# PHY.net
KiCad netlist of a schematic drawn in Altium Designer
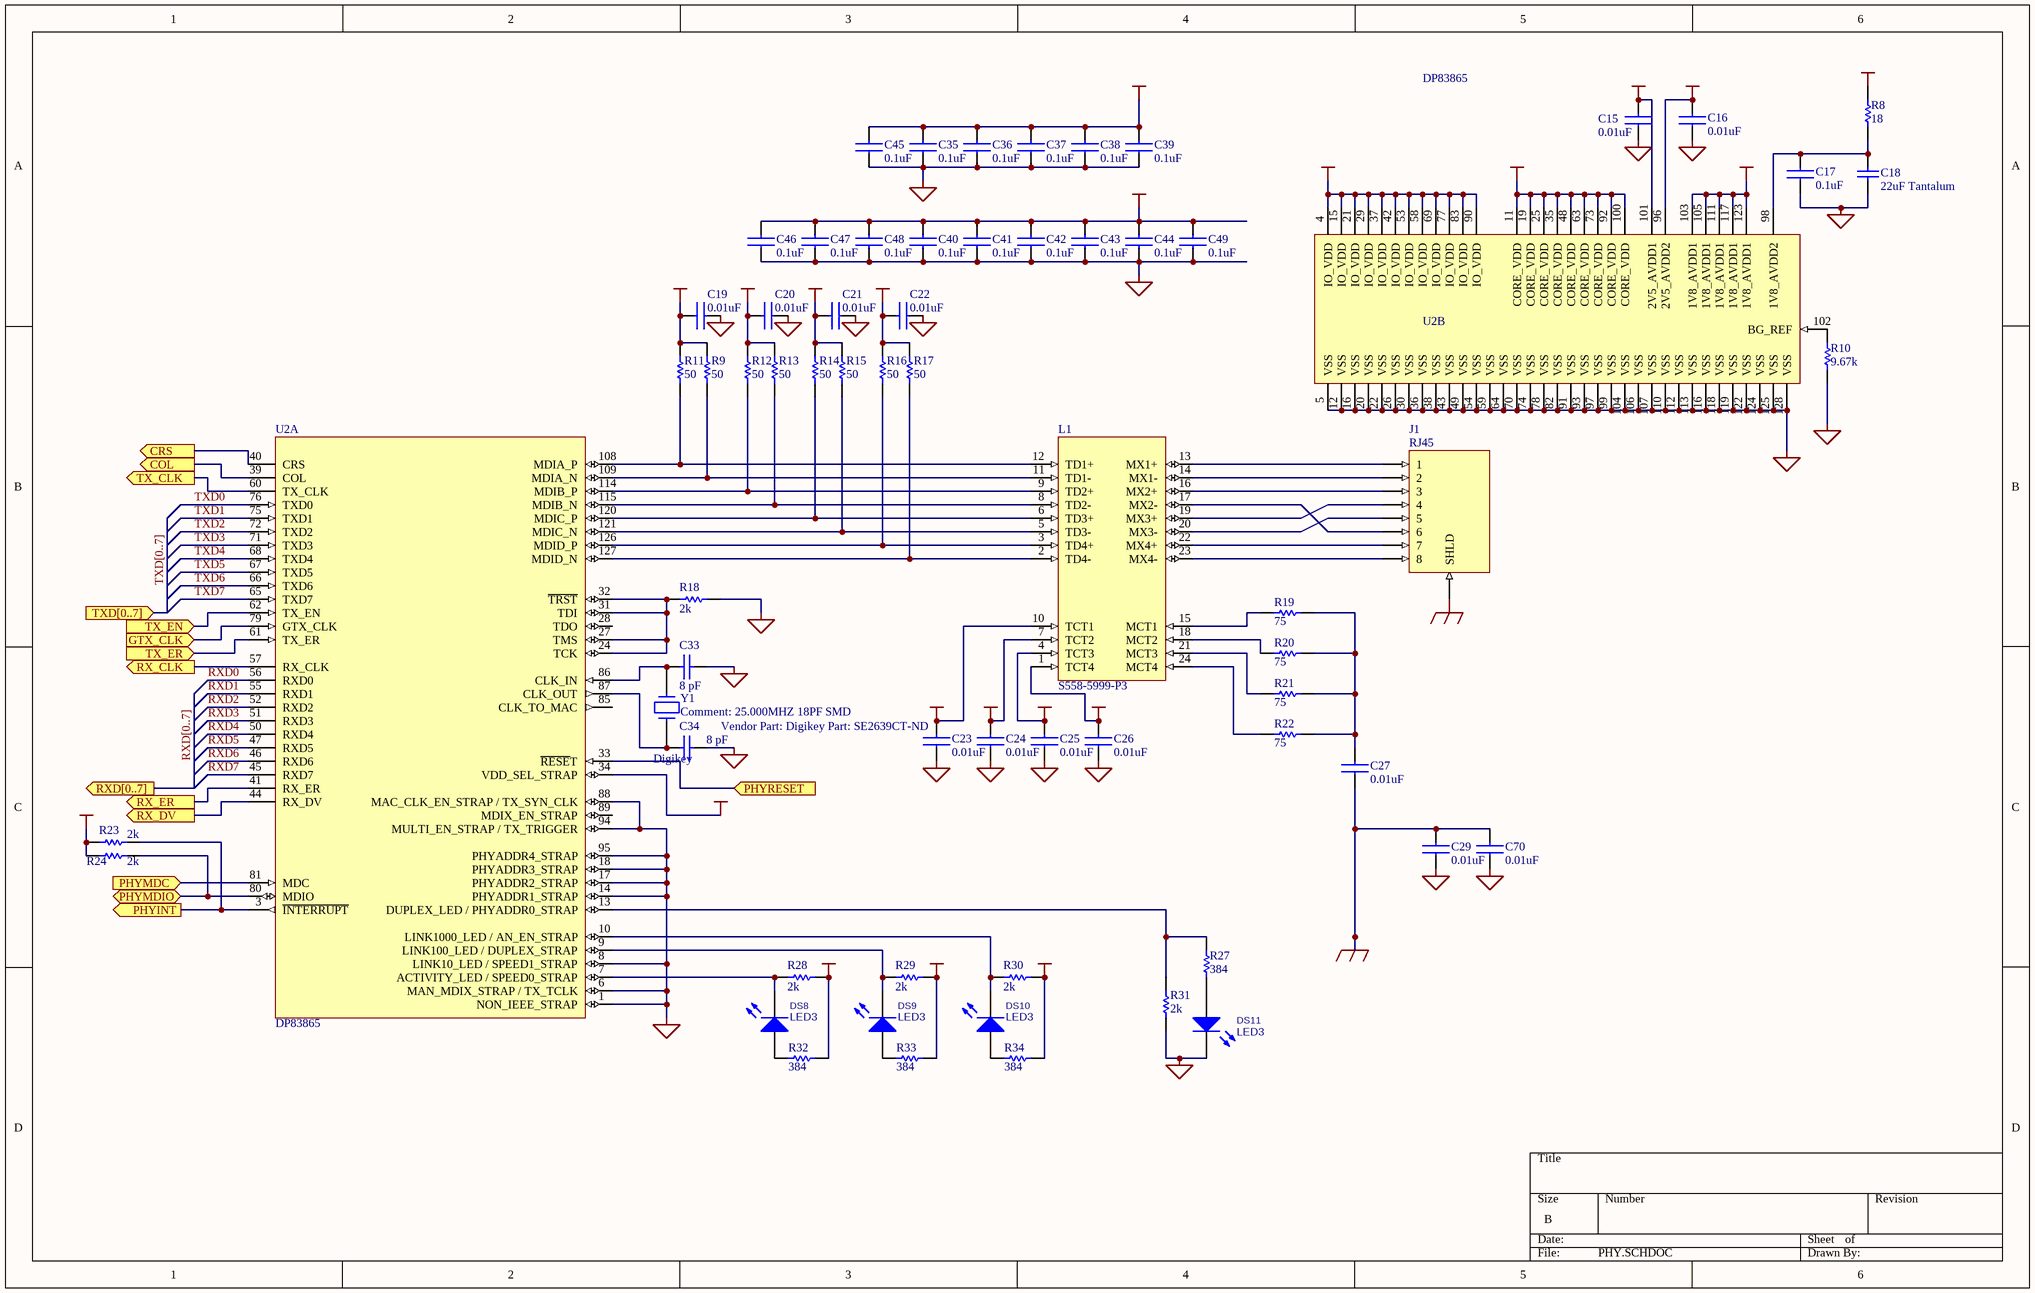
[diagram p0: PHY.SCHDOC]

(export (version "E")
  (design (tool "Eeschema 10.0.6"))
  (components
    (comp (ref "C15")
      (value "0.01uF")
      (footprint "0402")
      (description "Standard Capacitor")
      (fields (field (name "Comment") "CAPACITOR"))
      (libsource (lib "parts") (part "CAPACITOR"))
    )
    (comp (ref "C16")
      (value "0.01uF")
      (footprint "0402")
      (description "Standard Capacitor")
      (fields (field (name "Comment") "CAPACITOR"))
      (libsource (lib "parts") (part "CAPACITOR"))
    )
    (comp (ref "C17")
      (value "0.1uF")
      (footprint "0603")
      (description "Standard Capacitor")
      (fields (field (name "Comment") "CAPACITOR"))
      (libsource (lib "parts") (part "CAPACITOR"))
    )
    (comp (ref "C18")
      (value "22uF Tantalum")
      (footprint "TC7343-2917")
      (description "Capacitor")
      (fields
        (field (name "MANUFACTURER") "Generic Components")
        (field (name "Comment") "Cap")
        (field (name "PUBLISHER") "Altium Limited")
      )
      (libsource (lib "Miscellaneous Devices") (part "Cap"))
    )
    (comp (ref "C19")
      (value "0.01uF")
      (footprint "0402")
      (description "Standard Capacitor")
      (fields (field (name "Comment") "CAPACITOR"))
      (libsource (lib "parts") (part "CAPACITOR"))
    )
    (comp (ref "C20")
      (value "0.01uF")
      (footprint "0402")
      (description "Standard Capacitor")
      (fields (field (name "Comment") "CAPACITOR"))
      (libsource (lib "parts") (part "CAPACITOR"))
    )
    (comp (ref "C21")
      (value "0.01uF")
      (footprint "0402")
      (description "Standard Capacitor")
      (fields (field (name "Comment") "CAPACITOR"))
      (libsource (lib "parts") (part "CAPACITOR"))
    )
    (comp (ref "C22")
      (value "0.01uF")
      (footprint "0402")
      (description "Standard Capacitor")
      (fields (field (name "Comment") "CAPACITOR"))
      (libsource (lib "parts") (part "CAPACITOR"))
    )
    (comp (ref "C23")
      (value "0.01uF")
      (footprint "0402")
      (description "Standard Capacitor")
      (fields (field (name "Comment") "CAPACITOR"))
      (libsource (lib "parts") (part "CAPACITOR"))
    )
    (comp (ref "C24")
      (value "0.01uF")
      (footprint "0402")
      (description "Standard Capacitor")
      (fields (field (name "Comment") "CAPACITOR"))
      (libsource (lib "parts") (part "CAPACITOR"))
    )
    (comp (ref "C25")
      (value "0.01uF")
      (footprint "0402")
      (description "Standard Capacitor")
      (fields (field (name "Comment") "CAPACITOR"))
      (libsource (lib "parts") (part "CAPACITOR"))
    )
    (comp (ref "C26")
      (value "0.01uF")
      (footprint "0402")
      (description "Standard Capacitor")
      (fields (field (name "Comment") "CAPACITOR"))
      (libsource (lib "parts") (part "CAPACITOR"))
    )
    (comp (ref "C27")
      (value "0.01uF")
      (footprint "0402")
      (description "Standard Capacitor")
      (fields (field (name "Comment") "CAPACITOR"))
      (libsource (lib "parts") (part "CAPACITOR"))
    )
    (comp (ref "C29")
      (value "0.01uF")
      (footprint "0402")
      (description "Standard Capacitor")
      (fields (field (name "Comment") "CAPACITOR"))
      (libsource (lib "parts") (part "CAPACITOR"))
    )
    (comp (ref "C33")
      (value "8 pF")
      (footprint "0603")
      (description "Capacitor")
      (libsource (lib "*") (part "CAP"))
    )
    (comp (ref "C34")
      (value "8 pF")
      (footprint "0603")
      (description "Capacitor")
      (libsource (lib "*") (part "CAP"))
    )
    (comp (ref "C35")
      (value "0.1uF")
      (footprint "0603")
      (description "Standard Capacitor")
      (fields (field (name "Comment") "CAPACITOR"))
      (libsource (lib "parts") (part "CAPACITOR"))
    )
    (comp (ref "C36")
      (value "0.1uF")
      (footprint "0603")
      (description "Standard Capacitor")
      (fields (field (name "Comment") "CAPACITOR"))
      (libsource (lib "parts") (part "CAPACITOR"))
    )
    (comp (ref "C37")
      (value "0.1uF")
      (footprint "0603")
      (description "Standard Capacitor")
      (fields (field (name "Comment") "CAPACITOR"))
      (libsource (lib "parts") (part "CAPACITOR"))
    )
    (comp (ref "C38")
      (value "0.1uF")
      (footprint "0603")
      (description "Standard Capacitor")
      (fields (field (name "Comment") "CAPACITOR"))
      (libsource (lib "parts") (part "CAPACITOR"))
    )
    (comp (ref "C39")
      (value "0.1uF")
      (footprint "0603")
      (description "Standard Capacitor")
      (fields (field (name "Comment") "CAPACITOR"))
      (libsource (lib "parts") (part "CAPACITOR"))
    )
    (comp (ref "C40")
      (value "0.1uF")
      (footprint "0603")
      (description "Standard Capacitor")
      (fields (field (name "Comment") "CAPACITOR"))
      (libsource (lib "parts") (part "CAPACITOR"))
    )
    (comp (ref "C41")
      (value "0.1uF")
      (footprint "0603")
      (description "Standard Capacitor")
      (fields (field (name "Comment") "CAPACITOR"))
      (libsource (lib "parts") (part "CAPACITOR"))
    )
    (comp (ref "C42")
      (value "0.1uF")
      (footprint "0603")
      (description "Standard Capacitor")
      (fields (field (name "Comment") "CAPACITOR"))
      (libsource (lib "parts") (part "CAPACITOR"))
    )
    (comp (ref "C43")
      (value "0.1uF")
      (footprint "0603")
      (description "Standard Capacitor")
      (fields (field (name "Comment") "CAPACITOR"))
      (libsource (lib "parts") (part "CAPACITOR"))
    )
    (comp (ref "C44")
      (value "0.1uF")
      (footprint "0603")
      (description "Standard Capacitor")
      (fields (field (name "Comment") "CAPACITOR"))
      (libsource (lib "parts") (part "CAPACITOR"))
    )
    (comp (ref "C45")
      (value "0.1uF")
      (footprint "0603")
      (description "Standard Capacitor")
      (fields (field (name "Comment") "CAPACITOR"))
      (libsource (lib "parts") (part "CAPACITOR"))
    )
    (comp (ref "C46")
      (value "0.1uF")
      (footprint "0603")
      (description "Standard Capacitor")
      (fields (field (name "Comment") "CAPACITOR"))
      (libsource (lib "parts") (part "CAPACITOR"))
    )
    (comp (ref "C47")
      (value "0.1uF")
      (footprint "0603")
      (description "Standard Capacitor")
      (fields (field (name "Comment") "CAPACITOR"))
      (libsource (lib "parts") (part "CAPACITOR"))
    )
    (comp (ref "C48")
      (value "0.1uF")
      (footprint "0603")
      (description "Standard Capacitor")
      (fields (field (name "Comment") "CAPACITOR"))
      (libsource (lib "parts") (part "CAPACITOR"))
    )
    (comp (ref "C49")
      (value "0.1uF")
      (footprint "0603")
      (description "Standard Capacitor")
      (fields (field (name "Comment") "CAPACITOR"))
      (libsource (lib "parts") (part "CAPACITOR"))
    )
    (comp (ref "C70")
      (value "0.01uF")
      (footprint "0402")
      (description "Standard Capacitor")
      (fields (field (name "Comment") "CAPACITOR"))
      (libsource (lib "parts") (part "CAPACITOR"))
    )
    (comp (ref "DS8")
      (value "LED3")
      (footprint "SMD _LED")
      (description "Typical BLUE SiC LED")
      (fields (field (name "PUBLISHER") "Altium Limited"))
      (libsource (lib "Miscellaneous Devices") (part "LED3"))
    )
    (comp (ref "DS9")
      (value "LED3")
      (footprint "SMD _LED")
      (description "Typical BLUE SiC LED")
      (fields (field (name "PUBLISHER") "Altium Limited"))
      (libsource (lib "Miscellaneous Devices") (part "LED3"))
    )
    (comp (ref "DS10")
      (value "LED3")
      (footprint "SMD _LED")
      (description "Typical BLUE SiC LED")
      (fields (field (name "PUBLISHER") "Altium Limited"))
      (libsource (lib "Miscellaneous Devices") (part "LED3"))
    )
    (comp (ref "DS11")
      (value "LED3")
      (footprint "SMD _LED")
      (description "Typical BLUE SiC LED")
      (fields (field (name "PUBLISHER") "Altium Limited"))
      (libsource (lib "Miscellaneous Devices") (part "LED3"))
    )
    (comp (ref "J1")
      (value "RJ45")
      (footprint "MOLEXRJ45_44050-0007")
      (description "RJ-45 connector")
      (libsource (lib "*") (part "RJ45"))
    )
    (comp (ref "L1")
      (value "S558-5999-P3")
      (footprint "S558-5999-P3")
      (description "BEL 1000base-T magnetics S588-5999-P3")
      (libsource (lib "My devices") (part "S558-5999-P3"))
    )
    (comp (ref "R8")
      (value "18")
      (footprint "0603")
      (description "Resistor")
      (fields
        (field (name "MANUFACTURER") "Generic Components")
        (field (name "Comment") "Res1")
        (field (name "PUBLISHER") "Altium Limited")
      )
      (libsource (lib "Miscellaneous Devices") (part "Res1"))
    )
    (comp (ref "R9")
      (value "50")
      (footprint "0603")
      (description "Standard Passive Resistor")
      (fields (field (name "TOLERANCE") "1%") (field (name "Comment") "RESISTOR"))
      (libsource (lib "parts") (part "RESISTOR"))
    )
    (comp (ref "R10")
      (value "9.67k")
      (footprint "0603")
      (description "Resistor")
      (fields
        (field (name "MANUFACTURER") "Generic Components")
        (field (name "Comment") "Res1")
        (field (name "PUBLISHER") "Altium Limited")
      )
      (libsource (lib "Miscellaneous Devices") (part "Res1"))
    )
    (comp (ref "R11")
      (value "50")
      (footprint "0603")
      (description "Standard Passive Resistor")
      (fields (field (name "TOLERANCE") "1%") (field (name "Comment") "RESISTOR"))
      (libsource (lib "parts") (part "RESISTOR"))
    )
    (comp (ref "R12")
      (value "50")
      (footprint "0603")
      (description "Standard Passive Resistor")
      (fields (field (name "TOLERANCE") "1%") (field (name "Comment") "RESISTOR"))
      (libsource (lib "parts") (part "RESISTOR"))
    )
    (comp (ref "R13")
      (value "50")
      (footprint "0603")
      (description "Standard Passive Resistor")
      (fields (field (name "TOLERANCE") "1%") (field (name "Comment") "RESISTOR"))
      (libsource (lib "parts") (part "RESISTOR"))
    )
    (comp (ref "R14")
      (value "50")
      (footprint "0603")
      (description "Standard Passive Resistor")
      (fields (field (name "TOLERANCE") "1%") (field (name "Comment") "RESISTOR"))
      (libsource (lib "parts") (part "RESISTOR"))
    )
    (comp (ref "R15")
      (value "50")
      (footprint "0603")
      (description "Standard Passive Resistor")
      (fields (field (name "TOLERANCE") "1%") (field (name "Comment") "RESISTOR"))
      (libsource (lib "parts") (part "RESISTOR"))
    )
    (comp (ref "R16")
      (value "50")
      (footprint "0603")
      (description "Standard Passive Resistor")
      (fields (field (name "TOLERANCE") "1%") (field (name "Comment") "RESISTOR"))
      (libsource (lib "parts") (part "RESISTOR"))
    )
    (comp (ref "R17")
      (value "50")
      (footprint "0603")
      (description "Standard Passive Resistor")
      (fields (field (name "TOLERANCE") "1%") (field (name "Comment") "RESISTOR"))
      (libsource (lib "parts") (part "RESISTOR"))
    )
    (comp (ref "R18")
      (value "2k")
      (footprint "0603")
      (description "Standard Passive Resistor")
      (fields (field (name "TOLERANCE") "1%") (field (name "Comment") "RESISTOR"))
      (libsource (lib "parts") (part "RESISTOR"))
    )
    (comp (ref "R19")
      (value "75")
      (footprint "0603")
      (description "Resistor")
      (fields
        (field (name "MANUFACTURER") "Generic Components")
        (field (name "Comment") "Res1")
        (field (name "PUBLISHER") "Altium Limited")
      )
      (libsource (lib "Miscellaneous Devices") (part "Res1"))
    )
    (comp (ref "R20")
      (value "75")
      (footprint "0603")
      (description "Resistor")
      (fields
        (field (name "MANUFACTURER") "Generic Components")
        (field (name "Comment") "Res1")
        (field (name "PUBLISHER") "Altium Limited")
      )
      (libsource (lib "Miscellaneous Devices") (part "Res1"))
    )
    (comp (ref "R21")
      (value "75")
      (footprint "0603")
      (description "Resistor")
      (fields
        (field (name "MANUFACTURER") "Generic Components")
        (field (name "Comment") "Res1")
        (field (name "PUBLISHER") "Altium Limited")
      )
      (libsource (lib "Miscellaneous Devices") (part "Res1"))
    )
    (comp (ref "R22")
      (value "75")
      (footprint "0603")
      (description "Resistor")
      (fields
        (field (name "MANUFACTURER") "Generic Components")
        (field (name "Comment") "Res1")
        (field (name "PUBLISHER") "Altium Limited")
      )
      (libsource (lib "Miscellaneous Devices") (part "Res1"))
    )
    (comp (ref "R23")
      (value "2k")
      (footprint "0603")
      (description "Standard Passive Resistor")
      (fields (field (name "TOLERANCE") "1%") (field (name "Comment") "RESISTOR"))
      (libsource (lib "parts") (part "RESISTOR"))
    )
    (comp (ref "R24")
      (value "2k")
      (footprint "0603")
      (description "Standard Passive Resistor")
      (fields (field (name "TOLERANCE") "1%") (field (name "Comment") "RESISTOR"))
      (libsource (lib "parts") (part "RESISTOR"))
    )
    (comp (ref "R27")
      (value "384")
      (footprint "0603")
      (description "Resistor")
      (fields
        (field (name "MANUFACTURER") "Generic Components")
        (field (name "Comment") "Res1")
        (field (name "PUBLISHER") "Altium Limited")
      )
      (libsource (lib "Miscellaneous Devices") (part "Res1"))
    )
    (comp (ref "R28")
      (value "2k")
      (footprint "0603")
      (description "Standard Passive Resistor")
      (fields (field (name "TOLERANCE") "1%") (field (name "Comment") "RESISTOR"))
      (libsource (lib "parts") (part "RESISTOR"))
    )
    (comp (ref "R29")
      (value "2k")
      (footprint "0603")
      (description "Standard Passive Resistor")
      (fields (field (name "TOLERANCE") "1%") (field (name "Comment") "RESISTOR"))
      (libsource (lib "parts") (part "RESISTOR"))
    )
    (comp (ref "R30")
      (value "2k")
      (footprint "0603")
      (description "Standard Passive Resistor")
      (fields (field (name "TOLERANCE") "1%") (field (name "Comment") "RESISTOR"))
      (libsource (lib "parts") (part "RESISTOR"))
    )
    (comp (ref "R31")
      (value "2k")
      (footprint "0603")
      (description "Standard Passive Resistor")
      (fields (field (name "TOLERANCE") "1%") (field (name "Comment") "RESISTOR"))
      (libsource (lib "parts") (part "RESISTOR"))
    )
    (comp (ref "R32")
      (value "384")
      (footprint "0603")
      (description "Resistor")
      (fields
        (field (name "MANUFACTURER") "Generic Components")
        (field (name "Comment") "Res1")
        (field (name "PUBLISHER") "Altium Limited")
      )
      (libsource (lib "Miscellaneous Devices") (part "Res1"))
    )
    (comp (ref "R33")
      (value "384")
      (footprint "0603")
      (description "Resistor")
      (fields
        (field (name "MANUFACTURER") "Generic Components")
        (field (name "Comment") "Res1")
        (field (name "PUBLISHER") "Altium Limited")
      )
      (libsource (lib "Miscellaneous Devices") (part "Res1"))
    )
    (comp (ref "R34")
      (value "384")
      (footprint "0603")
      (description "Resistor")
      (fields
        (field (name "MANUFACTURER") "Generic Components")
        (field (name "Comment") "Res1")
        (field (name "PUBLISHER") "Altium Limited")
      )
      (libsource (lib "Miscellaneous Devices") (part "Res1"))
    )
    (comp (ref "U2")
      (value "DP83865")
      (footprint "PQFP128RECT")
      (description "National Semiconductor Gigabit PHY")
      (libsource (lib "My devices") (part "DP83865"))
    )
    (comp (ref "Y1")
      (value "25.000MHZ 18PF SMD")
      (footprint "EPSON_MA-506")
      (description "Crystal MA-506 25.000M-C0")
      (fields (field (name "VENDOR PART") "Digikey Part: SE2639CT-ND") (field (name "VENDOR") "Digikey"))
      (libsource (lib "*") (part "CRYSTAL"))
    )
  )
  (nets
    (net (code "1") (name "+1.8VCC") (class "Default")
      (node (ref "C40") (pin "1") (pintype "passive"))
      (node (ref "C41") (pin "1") (pintype "passive"))
      (node (ref "C42") (pin "1") (pintype "passive"))
      (node (ref "C43") (pin "1") (pintype "passive"))
      (node (ref "C44") (pin "1") (pintype "passive"))
      (node (ref "C46") (pin "1") (pintype "passive"))
      (node (ref "C47") (pin "1") (pintype "passive"))
      (node (ref "C48") (pin "1") (pintype "passive"))
      (node (ref "C49") (pin "1") (pintype "passive"))
      (node (ref "R8") (pin "2") (pinfunction "2_2") (pintype "passive"))
      (node (ref "U2") (pin "100") (pinfunction "CORE_VDD_100") (pintype "power_in"))
      (node (ref "U2") (pin "103") (pinfunction "1V8_AVDD1_103") (pintype "power_in"))
      (node (ref "U2") (pin "105") (pinfunction "1V8_AVDD1_105") (pintype "power_in"))
      (node (ref "U2") (pin "11") (pinfunction "CORE_VDD_11") (pintype "power_in"))
      (node (ref "U2") (pin "111") (pinfunction "1V8_AVDD1_111") (pintype "power_in"))
      (node (ref "U2") (pin "117") (pinfunction "1V8_AVDD1_117") (pintype "power_in"))
      (node (ref "U2") (pin "123") (pinfunction "1V8_AVDD1_123") (pintype "power_in"))
      (node (ref "U2") (pin "19") (pinfunction "CORE_VDD_19") (pintype "power_in"))
      (node (ref "U2") (pin "25") (pinfunction "CORE_VDD_25") (pintype "power_in"))
      (node (ref "U2") (pin "35") (pinfunction "CORE_VDD_35") (pintype "power_in"))
      (node (ref "U2") (pin "48") (pinfunction "CORE_VDD_48") (pintype "power_in"))
      (node (ref "U2") (pin "63") (pinfunction "CORE_VDD_63") (pintype "power_in"))
      (node (ref "U2") (pin "73") (pinfunction "CORE_VDD_73") (pintype "power_in"))
      (node (ref "U2") (pin "92") (pinfunction "CORE_VDD_92") (pintype "power_in"))
    )
    (net (code "2") (name "+2.5VPHY") (class "Default")
      (node (ref "C15") (pin "2") (pintype "passive"))
      (node (ref "C16") (pin "2") (pintype "passive"))
      (node (ref "C19") (pin "1") (pintype "passive"))
      (node (ref "C20") (pin "1") (pintype "passive"))
      (node (ref "C21") (pin "1") (pintype "passive"))
      (node (ref "C22") (pin "1") (pintype "passive"))
      (node (ref "C23") (pin "2") (pintype "passive"))
      (node (ref "C24") (pin "2") (pintype "passive"))
      (node (ref "C25") (pin "2") (pintype "passive"))
      (node (ref "C26") (pin "2") (pintype "passive"))
      (node (ref "L1") (pin "1") (pinfunction "TCT4_1") (pintype "input"))
      (node (ref "L1") (pin "10") (pinfunction "TCT1_10") (pintype "input"))
      (node (ref "L1") (pin "4") (pinfunction "TCT3_4") (pintype "input"))
      (node (ref "L1") (pin "7") (pinfunction "TCT2_7") (pintype "input"))
      (node (ref "R11") (pin "2") (pintype "passive"))
      (node (ref "R12") (pin "2") (pintype "passive"))
      (node (ref "R13") (pin "2") (pintype "passive"))
      (node (ref "R14") (pin "2") (pintype "passive"))
      (node (ref "R15") (pin "2") (pintype "passive"))
      (node (ref "R16") (pin "2") (pintype "passive"))
      (node (ref "R17") (pin "2") (pintype "passive"))
      (node (ref "R9") (pin "2") (pintype "passive"))
      (node (ref "U2") (pin "101") (pinfunction "2V5_AVDD1_101") (pintype "power_in"))
      (node (ref "U2") (pin "96") (pinfunction "2V5_AVDD2_96") (pintype "power_in"))
    )
    (net (code "3") (name "/COL") (class "Default")
      (node (ref "U2") (pin "39") (pinfunction "COL_39") (pintype "tri_state"))
    )
    (net (code "4") (name "/CRS") (class "Default")
      (node (ref "U2") (pin "40") (pinfunction "CRS_40") (pintype "tri_state"))
    )
    (net (code "5") (name "/GTX_CLK") (class "Default")
      (node (ref "U2") (pin "79") (pinfunction "GTX_CLK_79") (pintype "input"))
    )
    (net (code "6") (name "/PHYINT") (class "Default")
      (node (ref "R23") (pin "2") (pintype "passive"))
      (node (ref "U2") (pin "3") (pinfunction "~{INTERRUPT}_3") (pintype "output"))
    )
    (net (code "7") (name "/PHYMDC") (class "Default")
      (node (ref "U2") (pin "81") (pinfunction "MDC_81") (pintype "input"))
    )
    (net (code "8") (name "/PHYMDIO") (class "Default")
      (node (ref "R24") (pin "2") (pintype "passive"))
      (node (ref "U2") (pin "80") (pinfunction "MDIO_80") (pintype "bidirectional"))
    )
    (net (code "9") (name "/PHYRESET") (class "Default")
      (node (ref "U2") (pin "33") (pinfunction "~{RESE}T_33") (pintype "input"))
    )
    (net (code "10") (name "/RXD0") (class "Default")
      (node (ref "U2") (pin "56") (pinfunction "RXD0_56") (pintype "tri_state"))
    )
    (net (code "11") (name "/RXD1") (class "Default")
      (node (ref "U2") (pin "55") (pinfunction "RXD1_55") (pintype "tri_state"))
    )
    (net (code "12") (name "/RXD2") (class "Default")
      (node (ref "U2") (pin "52") (pinfunction "RXD2_52") (pintype "tri_state"))
    )
    (net (code "13") (name "/RXD3") (class "Default")
      (node (ref "U2") (pin "51") (pinfunction "RXD3_51") (pintype "tri_state"))
    )
    (net (code "14") (name "/RXD4") (class "Default")
      (node (ref "U2") (pin "50") (pinfunction "RXD4_50") (pintype "tri_state"))
    )
    (net (code "15") (name "/RXD5") (class "Default")
      (node (ref "U2") (pin "47") (pinfunction "RXD5_47") (pintype "tri_state"))
    )
    (net (code "16") (name "/RXD6") (class "Default")
      (node (ref "U2") (pin "46") (pinfunction "RXD6_46") (pintype "tri_state"))
    )
    (net (code "17") (name "/RXD7") (class "Default")
      (node (ref "U2") (pin "45") (pinfunction "RXD7_45") (pintype "tri_state"))
    )
    (net (code "19") (name "/RX_CLK") (class "Default")
      (node (ref "U2") (pin "57") (pinfunction "RX_CLK_57") (pintype "tri_state"))
    )
    (net (code "20") (name "/RX_DV") (class "Default")
      (node (ref "U2") (pin "44") (pinfunction "RX_DV_44") (pintype "tri_state"))
    )
    (net (code "21") (name "/RX_ER") (class "Default")
      (node (ref "U2") (pin "41") (pinfunction "RX_ER_41") (pintype "tri_state"))
    )
    (net (code "22") (name "/TXD0") (class "Default")
      (node (ref "U2") (pin "76") (pinfunction "TXD0_76") (pintype "input"))
    )
    (net (code "23") (name "/TXD1") (class "Default")
      (node (ref "U2") (pin "75") (pinfunction "TXD1_75") (pintype "input"))
    )
    (net (code "24") (name "/TXD2") (class "Default")
      (node (ref "U2") (pin "72") (pinfunction "TXD2_72") (pintype "input"))
    )
    (net (code "25") (name "/TXD3") (class "Default")
      (node (ref "U2") (pin "71") (pinfunction "TXD3_71") (pintype "input"))
    )
    (net (code "26") (name "/TXD4") (class "Default")
      (node (ref "U2") (pin "68") (pinfunction "TXD4_68") (pintype "input"))
    )
    (net (code "27") (name "/TXD5") (class "Default")
      (node (ref "U2") (pin "67") (pinfunction "TXD5_67") (pintype "input"))
    )
    (net (code "28") (name "/TXD6") (class "Default")
      (node (ref "U2") (pin "66") (pinfunction "TXD6_66") (pintype "input"))
    )
    (net (code "29") (name "/TXD7") (class "Default")
      (node (ref "U2") (pin "65") (pinfunction "TXD7_65") (pintype "input"))
    )
    (net (code "31") (name "/TX_CLK") (class "Default")
      (node (ref "U2") (pin "60") (pinfunction "TX_CLK_60") (pintype "tri_state"))
    )
    (net (code "32") (name "/TX_EN") (class "Default")
      (node (ref "U2") (pin "62") (pinfunction "TX_EN_62") (pintype "input"))
    )
    (net (code "33") (name "/TX_ER") (class "Default")
      (node (ref "U2") (pin "61") (pinfunction "TX_ER_61") (pintype "input"))
    )
    (net (code "34") (name "CGND") (class "Default")
      (node (ref "C27") (pin "1") (pintype "passive"))
      (node (ref "C29") (pin "2") (pintype "passive"))
      (node (ref "C70") (pin "2") (pintype "passive"))
      (node (ref "J1") (pin "9") (pinfunction "SHLD_9") (pintype "input"))
    )
    (net (code "35") (name "GND") (class "Default")
      (node (ref "C15") (pin "1") (pintype "passive"))
      (node (ref "C16") (pin "1") (pintype "passive"))
      (node (ref "C17") (pin "1") (pintype "passive"))
      (node (ref "C18") (pin "1") (pinfunction "1_1") (pintype "passive"))
      (node (ref "C19") (pin "2") (pintype "passive"))
      (node (ref "C20") (pin "2") (pintype "passive"))
      (node (ref "C21") (pin "2") (pintype "passive"))
      (node (ref "C22") (pin "2") (pintype "passive"))
      (node (ref "C23") (pin "1") (pintype "passive"))
      (node (ref "C24") (pin "1") (pintype "passive"))
      (node (ref "C25") (pin "1") (pintype "passive"))
      (node (ref "C26") (pin "1") (pintype "passive"))
      (node (ref "C29") (pin "1") (pintype "passive"))
      (node (ref "C33") (pin "2") (pinfunction "2_2") (pintype "passive"))
      (node (ref "C34") (pin "2") (pinfunction "2_2") (pintype "passive"))
      (node (ref "C35") (pin "2") (pintype "passive"))
      (node (ref "C36") (pin "2") (pintype "passive"))
      (node (ref "C37") (pin "2") (pintype "passive"))
      (node (ref "C38") (pin "2") (pintype "passive"))
      (node (ref "C39") (pin "2") (pintype "passive"))
      (node (ref "C40") (pin "2") (pintype "passive"))
      (node (ref "C41") (pin "2") (pintype "passive"))
      (node (ref "C42") (pin "2") (pintype "passive"))
      (node (ref "C43") (pin "2") (pintype "passive"))
      (node (ref "C44") (pin "2") (pintype "passive"))
      (node (ref "C45") (pin "2") (pintype "passive"))
      (node (ref "C46") (pin "2") (pintype "passive"))
      (node (ref "C47") (pin "2") (pintype "passive"))
      (node (ref "C48") (pin "2") (pintype "passive"))
      (node (ref "C49") (pin "2") (pintype "passive"))
      (node (ref "C70") (pin "1") (pintype "passive"))
      (node (ref "DS11") (pin "2") (pinfunction "K_2") (pintype "passive"))
      (node (ref "R10") (pin "1") (pinfunction "1_1") (pintype "passive"))
      (node (ref "R18") (pin "2") (pintype "passive"))
      (node (ref "R31") (pin "1") (pintype "passive"))
      (node (ref "U2") (pin "1") (pinfunction "NON_IEEE_STRAP_1") (pintype "bidirectional"))
      (node (ref "U2") (pin "104") (pinfunction "VSS_104") (pintype "power_in"))
      (node (ref "U2") (pin "106") (pinfunction "VSS_106") (pintype "power_in"))
      (node (ref "U2") (pin "107") (pinfunction "VSS_107") (pintype "power_in"))
      (node (ref "U2") (pin "110") (pinfunction "VSS_110") (pintype "power_in"))
      (node (ref "U2") (pin "112") (pinfunction "VSS_112") (pintype "power_in"))
      (node (ref "U2") (pin "113") (pinfunction "VSS_113") (pintype "power_in"))
      (node (ref "U2") (pin "116") (pinfunction "VSS_116") (pintype "power_in"))
      (node (ref "U2") (pin "118") (pinfunction "VSS_118") (pintype "power_in"))
      (node (ref "U2") (pin "119") (pinfunction "VSS_119") (pintype "power_in"))
      (node (ref "U2") (pin "12") (pinfunction "VSS_12") (pintype "power_in"))
      (node (ref "U2") (pin "122") (pinfunction "VSS_122") (pintype "power_in"))
      (node (ref "U2") (pin "124") (pinfunction "VSS_124") (pintype "power_in"))
      (node (ref "U2") (pin "125") (pinfunction "VSS_125") (pintype "power_in"))
      (node (ref "U2") (pin "128") (pinfunction "VSS_128") (pintype "power_in"))
      (node (ref "U2") (pin "14") (pinfunction "PHYADDR1_STRAP_14") (pintype "bidirectional"))
      (node (ref "U2") (pin "16") (pinfunction "VSS_16") (pintype "power_in"))
      (node (ref "U2") (pin "17") (pinfunction "PHYADDR2_STRAP_17") (pintype "bidirectional"))
      (node (ref "U2") (pin "18") (pinfunction "PHYADDR3_STRAP_18") (pintype "bidirectional"))
      (node (ref "U2") (pin "20") (pinfunction "VSS_20") (pintype "power_in"))
      (node (ref "U2") (pin "22") (pinfunction "VSS_22") (pintype "power_in"))
      (node (ref "U2") (pin "26") (pinfunction "VSS_26") (pintype "power_in"))
      (node (ref "U2") (pin "30") (pinfunction "VSS_30") (pintype "power_in"))
      (node (ref "U2") (pin "36") (pinfunction "VSS_36") (pintype "power_in"))
      (node (ref "U2") (pin "38") (pinfunction "VSS_38") (pintype "power_in"))
      (node (ref "U2") (pin "43") (pinfunction "VSS_43") (pintype "power_in"))
      (node (ref "U2") (pin "49") (pinfunction "VSS_49") (pintype "power_in"))
      (node (ref "U2") (pin "5") (pinfunction "VSS_5") (pintype "power_in"))
      (node (ref "U2") (pin "54") (pinfunction "VSS_54") (pintype "power_in"))
      (node (ref "U2") (pin "59") (pinfunction "VSS_59") (pintype "power_in"))
      (node (ref "U2") (pin "6") (pinfunction "MAN_MDIX_STRAP_/_TX_TCLK_6") (pintype "bidirectional"))
      (node (ref "U2") (pin "64") (pinfunction "VSS_64") (pintype "power_in"))
      (node (ref "U2") (pin "70") (pinfunction "VSS_70") (pintype "power_in"))
      (node (ref "U2") (pin "74") (pinfunction "VSS_74") (pintype "power_in"))
      (node (ref "U2") (pin "78") (pinfunction "VSS_78") (pintype "power_in"))
      (node (ref "U2") (pin "8") (pinfunction "LINK10_LED_/_SPEED1_STRAP_8") (pintype "bidirectional"))
      (node (ref "U2") (pin "82") (pinfunction "VSS_82") (pintype "power_in"))
      (node (ref "U2") (pin "88") (pinfunction "MAC_CLK_EN_STRAP_/_TX_SYN_CLK_88") (pintype "bidirectional"))
      (node (ref "U2") (pin "91") (pinfunction "VSS_91") (pintype "power_in"))
      (node (ref "U2") (pin "93") (pinfunction "VSS_93") (pintype "power_in"))
      (node (ref "U2") (pin "94") (pinfunction "MULTI_EN_STRAP_/_TX_TRIGGER_94") (pintype "bidirectional"))
      (node (ref "U2") (pin "95") (pinfunction "PHYADDR4_STRAP_95") (pintype "bidirectional"))
      (node (ref "U2") (pin "97") (pinfunction "VSS_97") (pintype "power_in"))
      (node (ref "U2") (pin "99") (pinfunction "VSS_99") (pintype "power_in"))
    )
    (net (code "36") (name "Net-(C27-Pad2)") (class "Default")
      (node (ref "C27") (pin "2") (pintype "passive"))
      (node (ref "R19") (pin "1") (pinfunction "1_1") (pintype "passive"))
      (node (ref "R20") (pin "1") (pinfunction "1_1") (pintype "passive"))
      (node (ref "R21") (pin "1") (pinfunction "1_1") (pintype "passive"))
      (node (ref "R22") (pin "1") (pinfunction "1_1") (pintype "passive"))
    )
    (net (code "37") (name "Net-(DS8-A)") (class "Default")
      (node (ref "DS8") (pin "1") (pinfunction "A_1") (pintype "passive"))
      (node (ref "R32") (pin "1") (pinfunction "1_1") (pintype "passive"))
    )
    (net (code "38") (name "Net-(DS8-K)") (class "Default")
      (node (ref "DS8") (pin "2") (pinfunction "K_2") (pintype "passive"))
      (node (ref "R28") (pin "1") (pintype "passive"))
      (node (ref "U2") (pin "7") (pinfunction "ACTIVITY_LED_/_SPEED0_STRAP_7") (pintype "bidirectional"))
    )
    (net (code "39") (name "Net-(DS9-A)") (class "Default")
      (node (ref "DS9") (pin "1") (pinfunction "A_1") (pintype "passive"))
      (node (ref "R33") (pin "1") (pinfunction "1_1") (pintype "passive"))
    )
    (net (code "40") (name "Net-(DS9-K)") (class "Default")
      (node (ref "DS9") (pin "2") (pinfunction "K_2") (pintype "passive"))
      (node (ref "R29") (pin "1") (pintype "passive"))
      (node (ref "U2") (pin "9") (pinfunction "LINK100_LED_/_DUPLEX_STRAP_9") (pintype "bidirectional"))
    )
    (net (code "41") (name "Net-(DS10-A)") (class "Default")
      (node (ref "DS10") (pin "1") (pinfunction "A_1") (pintype "passive"))
      (node (ref "R34") (pin "1") (pinfunction "1_1") (pintype "passive"))
    )
    (net (code "42") (name "Net-(DS10-K)") (class "Default")
      (node (ref "DS10") (pin "2") (pinfunction "K_2") (pintype "passive"))
      (node (ref "R30") (pin "1") (pintype "passive"))
      (node (ref "U2") (pin "10") (pinfunction "LINK1000_LED_/_AN_EN_STRAP_10") (pintype "bidirectional"))
    )
    (net (code "43") (name "Net-(DS11-A)") (class "Default")
      (node (ref "DS11") (pin "1") (pinfunction "A_1") (pintype "passive"))
      (node (ref "R27") (pin "1") (pinfunction "1_1") (pintype "passive"))
    )
    (net (code "44") (name "Net-(L1-MCT1)") (class "Default")
      (node (ref "L1") (pin "15") (pinfunction "MCT1_15") (pintype "input"))
      (node (ref "R19") (pin "2") (pinfunction "2_2") (pintype "passive"))
    )
    (net (code "45") (name "Net-(L1-MCT2)") (class "Default")
      (node (ref "L1") (pin "18") (pinfunction "MCT2_18") (pintype "input"))
      (node (ref "R20") (pin "2") (pinfunction "2_2") (pintype "passive"))
    )
    (net (code "46") (name "Net-(L1-MCT3)") (class "Default")
      (node (ref "L1") (pin "21") (pinfunction "MCT3_21") (pintype "input"))
      (node (ref "R21") (pin "2") (pinfunction "2_2") (pintype "passive"))
    )
    (net (code "47") (name "Net-(L1-MCT4)") (class "Default")
      (node (ref "L1") (pin "24") (pinfunction "MCT4_24") (pintype "input"))
      (node (ref "R22") (pin "2") (pinfunction "2_2") (pintype "passive"))
    )
    (net (code "48") (name "Net-(L1-MX1+)") (class "Default")
      (node (ref "J1") (pin "1") (pinfunction "1_1") (pintype "input"))
      (node (ref "L1") (pin "13") (pinfunction "MX1+_13") (pintype "bidirectional"))
    )
    (net (code "49") (name "Net-(L1-MX1-)") (class "Default")
      (node (ref "J1") (pin "2") (pinfunction "2_2") (pintype "input"))
      (node (ref "L1") (pin "14") (pinfunction "MX1-_14") (pintype "bidirectional"))
    )
    (net (code "50") (name "Net-(L1-MX2+)") (class "Default")
      (node (ref "J1") (pin "3") (pinfunction "3_3") (pintype "input"))
      (node (ref "L1") (pin "16") (pinfunction "MX2+_16") (pintype "bidirectional"))
    )
    (net (code "51") (name "Net-(L1-MX2-)") (class "Default")
      (node (ref "J1") (pin "6") (pinfunction "6_6") (pintype "input"))
      (node (ref "L1") (pin "17") (pinfunction "MX2-_17") (pintype "bidirectional"))
    )
    (net (code "52") (name "Net-(L1-MX3+)") (class "Default")
      (node (ref "J1") (pin "4") (pinfunction "4_4") (pintype "input"))
      (node (ref "L1") (pin "19") (pinfunction "MX3+_19") (pintype "bidirectional"))
    )
    (net (code "53") (name "Net-(L1-MX3-)") (class "Default")
      (node (ref "J1") (pin "5") (pinfunction "5_5") (pintype "input"))
      (node (ref "L1") (pin "20") (pinfunction "MX3-_20") (pintype "bidirectional"))
    )
    (net (code "54") (name "Net-(L1-MX4+)") (class "Default")
      (node (ref "J1") (pin "7") (pinfunction "7_7") (pintype "input"))
      (node (ref "L1") (pin "22") (pinfunction "MX4+_22") (pintype "bidirectional"))
    )
    (net (code "55") (name "Net-(L1-MX4-)") (class "Default")
      (node (ref "J1") (pin "8") (pinfunction "8_8") (pintype "input"))
      (node (ref "L1") (pin "23") (pinfunction "MX4-_23") (pintype "bidirectional"))
    )
    (net (code "56") (name "Net-(L1-TD1+)") (class "Default")
      (node (ref "L1") (pin "12") (pinfunction "TD1+_12") (pintype "input"))
      (node (ref "R11") (pin "1") (pintype "passive"))
      (node (ref "U2") (pin "108") (pinfunction "MDIA_P_108") (pintype "bidirectional"))
    )
    (net (code "57") (name "Net-(L1-TD1-)") (class "Default")
      (node (ref "L1") (pin "11") (pinfunction "TD1-_11") (pintype "input"))
      (node (ref "R9") (pin "1") (pintype "passive"))
      (node (ref "U2") (pin "109") (pinfunction "MDIA_N_109") (pintype "bidirectional"))
    )
    (net (code "58") (name "Net-(L1-TD2+)") (class "Default")
      (node (ref "L1") (pin "9") (pinfunction "TD2+_9") (pintype "input"))
      (node (ref "R12") (pin "1") (pintype "passive"))
      (node (ref "U2") (pin "114") (pinfunction "MDIB_P_114") (pintype "bidirectional"))
    )
    (net (code "59") (name "Net-(L1-TD2-)") (class "Default")
      (node (ref "L1") (pin "8") (pinfunction "TD2-_8") (pintype "input"))
      (node (ref "R13") (pin "1") (pintype "passive"))
      (node (ref "U2") (pin "115") (pinfunction "MDIB_N_115") (pintype "bidirectional"))
    )
    (net (code "60") (name "Net-(L1-TD3+)") (class "Default")
      (node (ref "L1") (pin "6") (pinfunction "TD3+_6") (pintype "input"))
      (node (ref "R14") (pin "1") (pintype "passive"))
      (node (ref "U2") (pin "120") (pinfunction "MDIC_P_120") (pintype "bidirectional"))
    )
    (net (code "61") (name "Net-(L1-TD3-)") (class "Default")
      (node (ref "L1") (pin "5") (pinfunction "TD3-_5") (pintype "input"))
      (node (ref "R15") (pin "1") (pintype "passive"))
      (node (ref "U2") (pin "121") (pinfunction "MDIC_N_121") (pintype "bidirectional"))
    )
    (net (code "62") (name "Net-(L1-TD4+)") (class "Default")
      (node (ref "L1") (pin "3") (pinfunction "TD4+_3") (pintype "input"))
      (node (ref "R16") (pin "1") (pintype "passive"))
      (node (ref "U2") (pin "126") (pinfunction "MDID_P_126") (pintype "bidirectional"))
    )
    (net (code "63") (name "Net-(L1-TD4-)") (class "Default")
      (node (ref "L1") (pin "2") (pinfunction "TD4-_2") (pintype "input"))
      (node (ref "R17") (pin "1") (pintype "passive"))
      (node (ref "U2") (pin "127") (pinfunction "MDID_N_127") (pintype "bidirectional"))
    )
    (net (code "64") (name "Net-(U2A-CLK_IN)") (class "Default")
      (node (ref "C33") (pin "1") (pinfunction "1_1") (pintype "passive"))
      (node (ref "U2") (pin "86") (pinfunction "CLK_IN_86") (pintype "input"))
      (node (ref "Y1") (pin "1") (pinfunction "1_1") (pintype "passive"))
    )
    (net (code "65") (name "Net-(U2A-CLK_OUT)") (class "Default")
      (node (ref "C34") (pin "1") (pinfunction "1_1") (pintype "passive"))
      (node (ref "U2") (pin "87") (pinfunction "CLK_OUT_87") (pintype "output"))
      (node (ref "Y1") (pin "2") (pinfunction "2_2") (pintype "passive"))
    )
    (net (code "66") (name "Net-(U2A-DUPLEX_LED_{slash}_PHYADDR0_STRAP)") (class "Default")
      (node (ref "R27") (pin "2") (pinfunction "2_2") (pintype "passive"))
      (node (ref "R31") (pin "2") (pintype "passive"))
      (node (ref "U2") (pin "13") (pinfunction "DUPLEX_LED_/_PHYADDR0_STRAP_13") (pintype "bidirectional"))
    )
    (net (code "67") (name "Net-(U2A-TCK)") (class "Default")
      (node (ref "R18") (pin "1") (pintype "passive"))
      (node (ref "U2") (pin "24") (pinfunction "TCK_24") (pintype "bidirectional"))
      (node (ref "U2") (pin "27") (pinfunction "TMS_27") (pintype "bidirectional"))
      (node (ref "U2") (pin "31") (pinfunction "TDI_31") (pintype "bidirectional"))
      (node (ref "U2") (pin "32") (pinfunction "~{TRST}_32") (pintype "bidirectional"))
    )
    (net (code "68") (name "Net-(U2B-1V8_AVDD2)") (class "Default")
      (node (ref "C17") (pin "2") (pintype "passive"))
      (node (ref "C18") (pin "2") (pinfunction "2_2") (pintype "passive"))
      (node (ref "R8") (pin "1") (pinfunction "1_1") (pintype "passive"))
      (node (ref "U2") (pin "98") (pinfunction "1V8_AVDD2_98") (pintype "power_in"))
    )
    (net (code "69") (name "Net-(U2B-BG_REF)") (class "Default")
      (node (ref "R10") (pin "2") (pinfunction "2_2") (pintype "passive"))
      (node (ref "U2") (pin "102") (pinfunction "BG_REF_102") (pintype "input"))
    )
    (net (code "70") (name "VCC") (class "Default")
      (node (ref "C35") (pin "1") (pintype "passive"))
      (node (ref "C36") (pin "1") (pintype "passive"))
      (node (ref "C37") (pin "1") (pintype "passive"))
      (node (ref "C38") (pin "1") (pintype "passive"))
      (node (ref "C39") (pin "1") (pintype "passive"))
      (node (ref "C45") (pin "1") (pintype "passive"))
      (node (ref "R23") (pin "1") (pintype "passive"))
      (node (ref "R24") (pin "1") (pintype "passive"))
      (node (ref "R28") (pin "2") (pintype "passive"))
      (node (ref "R29") (pin "2") (pintype "passive"))
      (node (ref "R30") (pin "2") (pintype "passive"))
      (node (ref "R32") (pin "2") (pinfunction "2_2") (pintype "passive"))
      (node (ref "R33") (pin "2") (pinfunction "2_2") (pintype "passive"))
      (node (ref "R34") (pin "2") (pinfunction "2_2") (pintype "passive"))
      (node (ref "U2") (pin "15") (pinfunction "IO_VDD_15") (pintype "power_in"))
      (node (ref "U2") (pin "21") (pinfunction "IO_VDD_21") (pintype "power_in"))
      (node (ref "U2") (pin "29") (pinfunction "IO_VDD_29") (pintype "power_in"))
      (node (ref "U2") (pin "34") (pinfunction "VDD_SEL_STRAP_34") (pintype "bidirectional"))
      (node (ref "U2") (pin "37") (pinfunction "IO_VDD_37") (pintype "power_in"))
      (node (ref "U2") (pin "4") (pinfunction "IO_VDD_4") (pintype "power_in"))
      (node (ref "U2") (pin "42") (pinfunction "IO_VDD_42") (pintype "power_in"))
      (node (ref "U2") (pin "53") (pinfunction "IO_VDD_53") (pintype "power_in"))
      (node (ref "U2") (pin "58") (pinfunction "IO_VDD_58") (pintype "power_in"))
      (node (ref "U2") (pin "69") (pinfunction "IO_VDD_69") (pintype "power_in"))
      (node (ref "U2") (pin "77") (pinfunction "IO_VDD_77") (pintype "power_in"))
      (node (ref "U2") (pin "83") (pinfunction "IO_VDD_83") (pintype "power_in"))
      (node (ref "U2") (pin "90") (pinfunction "IO_VDD_90") (pintype "power_in"))
    )
    (net (code "71") (name "unconnected-(U2A-CLK_TO_MAC-Pad85)") (class "Default")
      (node (ref "U2") (pin "85") (pinfunction "CLK_TO_MAC_85") (pintype "output"))
    )
    (net (code "72") (name "unconnected-(U2A-MDIX_EN_STRAP-Pad89)") (class "Default")
      (node (ref "U2") (pin "89") (pinfunction "MDIX_EN_STRAP_89") (pintype "bidirectional"))
    )
    (net (code "73") (name "unconnected-(U2A-TDO-Pad28)") (class "Default")
      (node (ref "U2") (pin "28") (pinfunction "TDO_28") (pintype "bidirectional"))
    )
  )
)
